# PSDT_Controller_v1_0_0.net
KiCad netlist of a schematic drawn in Altium Designer
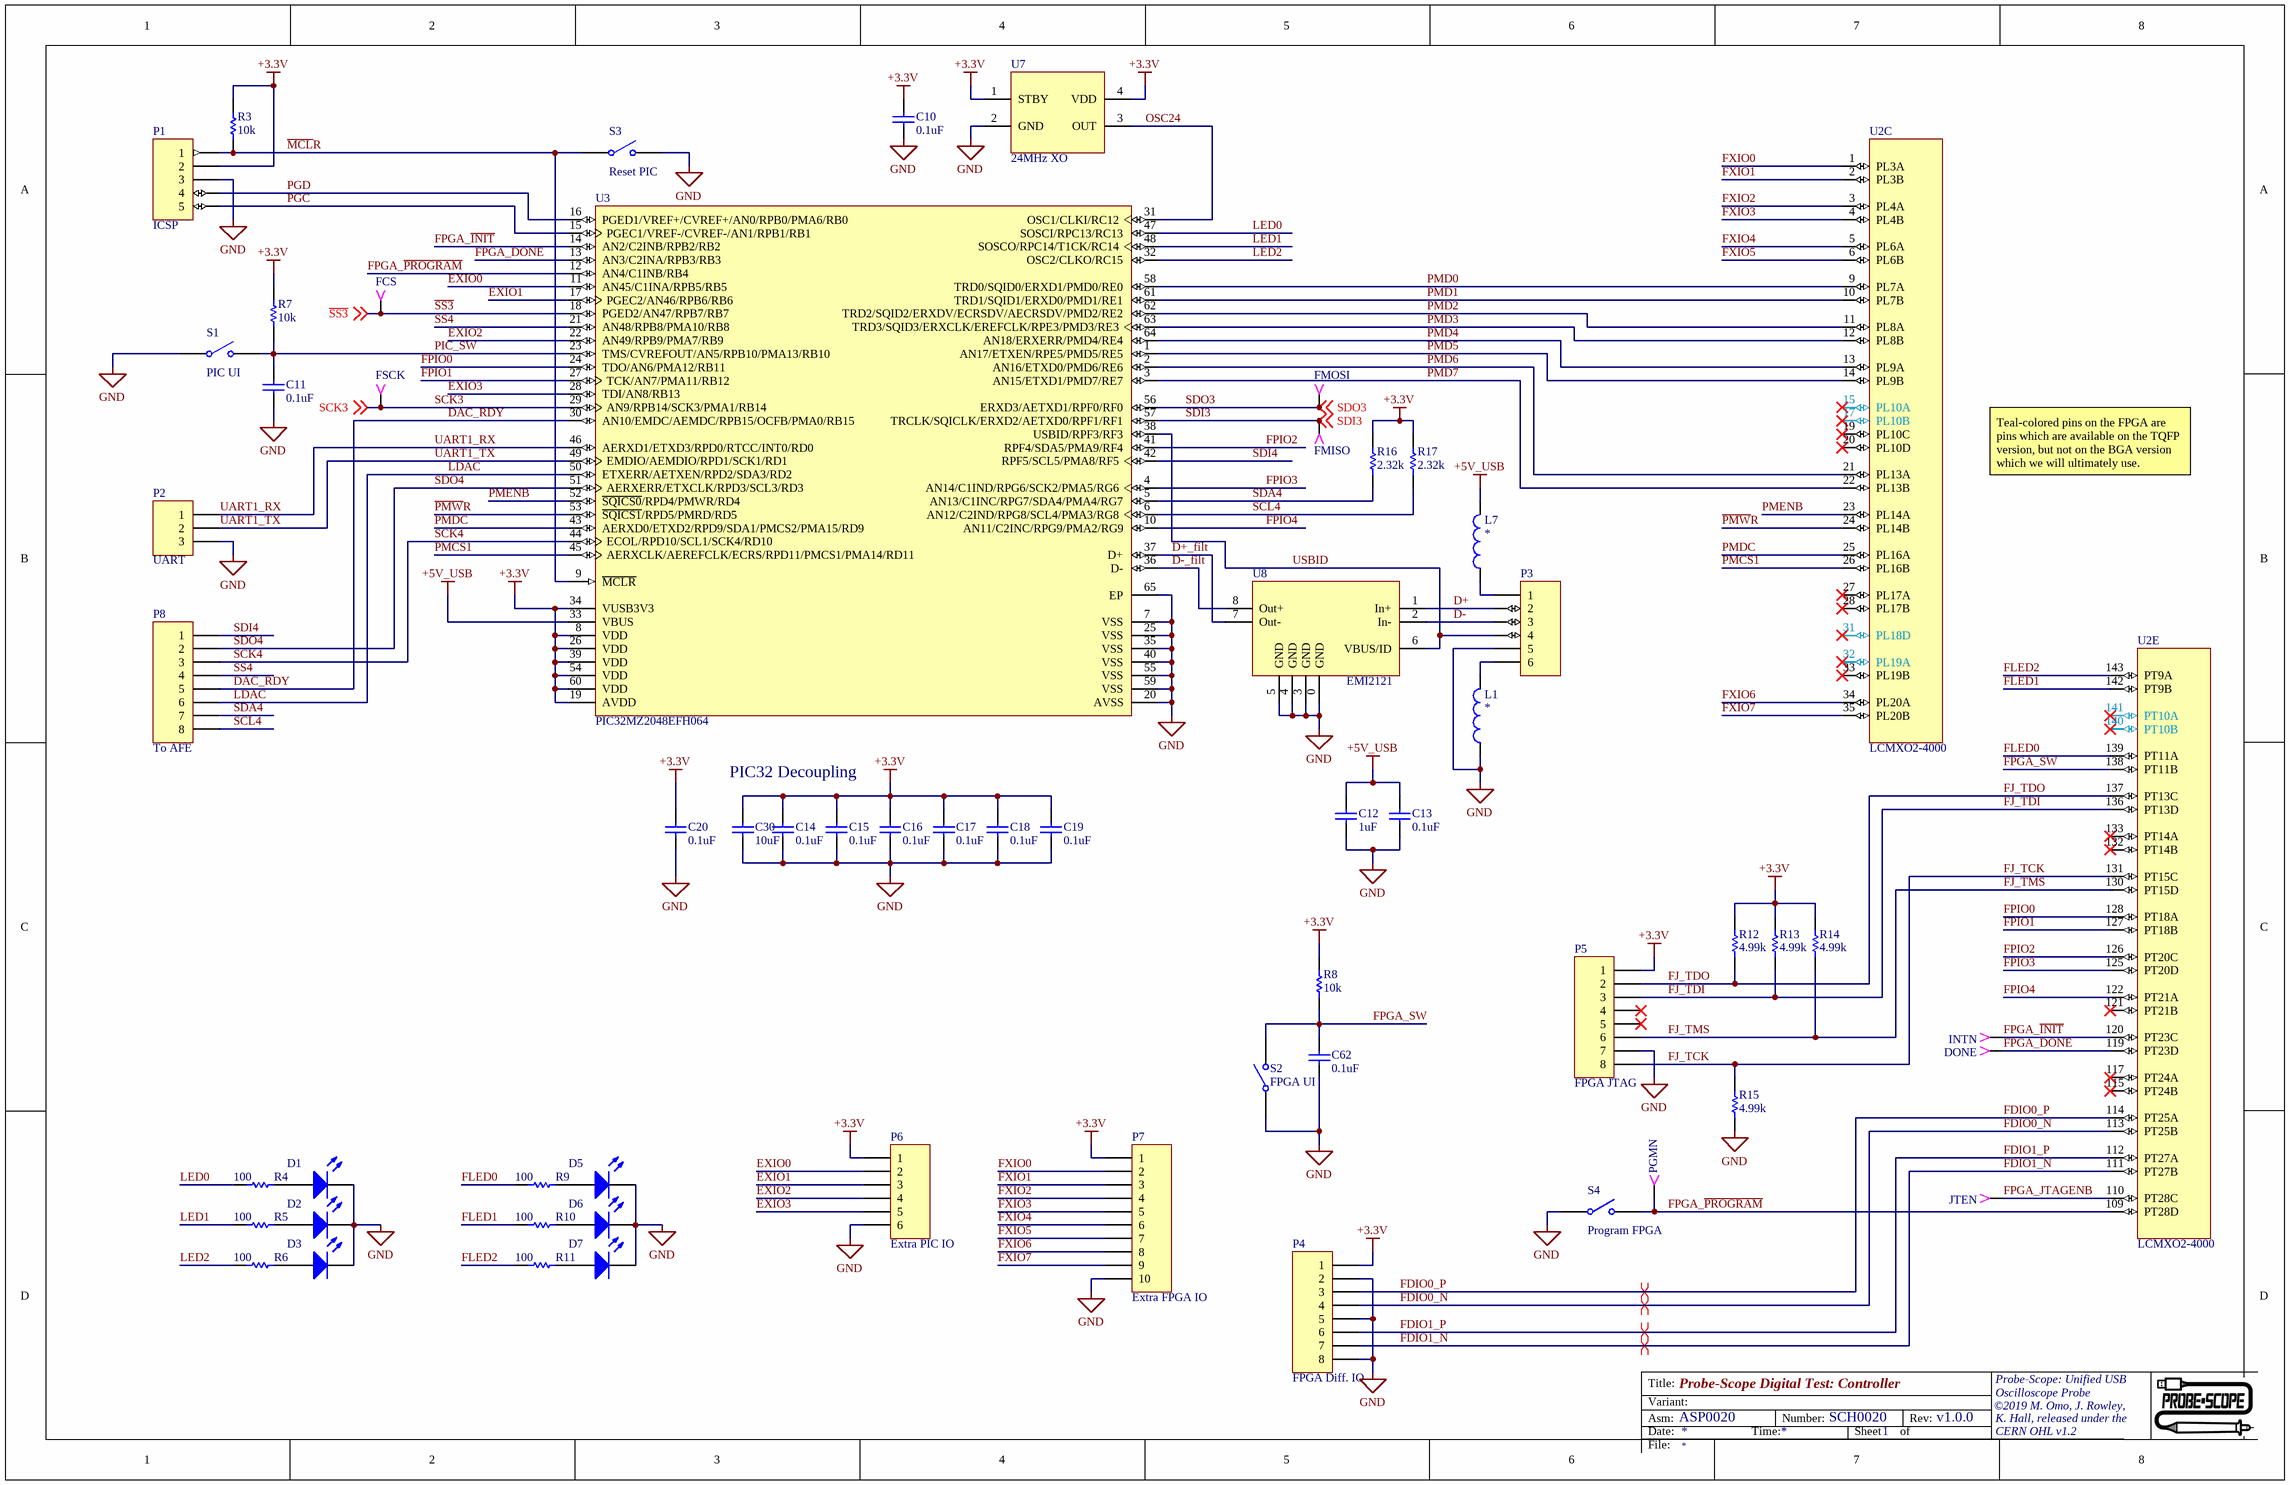
[diagram p0: PSDT Controller v1.0.0.SchDoc]

(export (version "E")
  (design (tool "Eeschema 10.0.6"))
  (components
    (comp (ref "C10")
      (value "0.1uF")
      (footprint "0402(1005)")
      (fields
        (field (name "MANF") "Samsung Electro-Mechanics")
        (field (name "TOLERANCE") "10")
        (field (name "VOLTAGE") "6.3")
        (field (name "MODIFIED BY") "jrowley")
        (field (name "APPROVED") "False")
      )
      (libsource (lib "MENG Database Library VPN") (part "Cap"))
    )
    (comp (ref "C11")
      (value "0.1uF")
      (footprint "0402(1005)")
      (fields
        (field (name "MANF") "Samsung Electro-Mechanics")
        (field (name "TOLERANCE") "10")
        (field (name "VOLTAGE") "6.3")
        (field (name "MODIFIED BY") "jrowley")
        (field (name "APPROVED") "False")
      )
      (libsource (lib "MENG Database Library VPN") (part "Cap"))
    )
    (comp (ref "C12")
      (value "1uF")
      (footprint "0402(1005)")
      (fields
        (field (name "MANF") "Murata Electronics")
        (field (name "TOLERANCE") "10")
        (field (name "Comment") "10V")
        (field (name "MODIFIED BY") "jrowley")
        (field (name "APPROVED") "False")
      )
      (libsource (lib "MENG Database Library VPN") (part "Cap"))
    )
    (comp (ref "C13")
      (value "0.1uF")
      (footprint "0402(1005)")
      (fields
        (field (name "MANF") "Samsung Electro-Mechanics")
        (field (name "TOLERANCE") "10")
        (field (name "VOLTAGE") "6.3")
        (field (name "MODIFIED BY") "jrowley")
        (field (name "APPROVED") "False")
      )
      (libsource (lib "MENG Database Library VPN") (part "Cap"))
    )
    (comp (ref "C14")
      (value "0.1uF")
      (footprint "0402(1005)")
      (fields
        (field (name "MANF") "Samsung Electro-Mechanics")
        (field (name "TOLERANCE") "10")
        (field (name "VOLTAGE") "6.3")
        (field (name "MODIFIED BY") "jrowley")
        (field (name "APPROVED") "False")
      )
      (libsource (lib "MENG Database Library VPN") (part "Cap"))
    )
    (comp (ref "C15")
      (value "0.1uF")
      (footprint "0402(1005)")
      (fields
        (field (name "MANF") "Samsung Electro-Mechanics")
        (field (name "TOLERANCE") "10")
        (field (name "VOLTAGE") "6.3")
        (field (name "MODIFIED BY") "jrowley")
        (field (name "APPROVED") "False")
      )
      (libsource (lib "MENG Database Library VPN") (part "Cap"))
    )
    (comp (ref "C16")
      (value "0.1uF")
      (footprint "0402(1005)")
      (fields
        (field (name "MANF") "Samsung Electro-Mechanics")
        (field (name "TOLERANCE") "10")
        (field (name "VOLTAGE") "6.3")
        (field (name "MODIFIED BY") "jrowley")
        (field (name "APPROVED") "False")
      )
      (libsource (lib "MENG Database Library VPN") (part "Cap"))
    )
    (comp (ref "C17")
      (value "0.1uF")
      (footprint "0402(1005)")
      (fields
        (field (name "MANF") "Samsung Electro-Mechanics")
        (field (name "TOLERANCE") "10")
        (field (name "VOLTAGE") "6.3")
        (field (name "MODIFIED BY") "jrowley")
        (field (name "APPROVED") "False")
      )
      (libsource (lib "MENG Database Library VPN") (part "Cap"))
    )
    (comp (ref "C18")
      (value "0.1uF")
      (footprint "0402(1005)")
      (fields
        (field (name "MANF") "Samsung Electro-Mechanics")
        (field (name "TOLERANCE") "10")
        (field (name "VOLTAGE") "6.3")
        (field (name "MODIFIED BY") "jrowley")
        (field (name "APPROVED") "False")
      )
      (libsource (lib "MENG Database Library VPN") (part "Cap"))
    )
    (comp (ref "C19")
      (value "0.1uF")
      (footprint "0402(1005)")
      (fields
        (field (name "MANF") "Samsung Electro-Mechanics")
        (field (name "TOLERANCE") "10")
        (field (name "VOLTAGE") "6.3")
        (field (name "MODIFIED BY") "jrowley")
        (field (name "APPROVED") "False")
      )
      (libsource (lib "MENG Database Library VPN") (part "Cap"))
    )
    (comp (ref "C20")
      (value "0.1uF")
      (footprint "0402(1005)")
      (fields
        (field (name "MANF") "Samsung Electro-Mechanics")
        (field (name "TOLERANCE") "10")
        (field (name "VOLTAGE") "6.3")
        (field (name "MODIFIED BY") "jrowley")
        (field (name "APPROVED") "False")
      )
      (libsource (lib "MENG Database Library VPN") (part "Cap"))
    )
    (comp (ref "C30")
      (value "10uF")
      (footprint "0603(1608)")
      (fields
        (field (name "MANF") "Samsung Electro-Mechanics")
        (field (name "TOLERANCE") "20")
        (field (name "VOLTAGE") "25")
        (field (name "MODIFIED BY") "sotterbacher")
        (field (name "APPROVED") "True")
      )
      (libsource (lib "MENG Database Library VPN") (part "Cap"))
    )
    (comp (ref "C62")
      (value "0.1uF")
      (footprint "0402(1005)")
      (fields
        (field (name "MANF") "Samsung Electro-Mechanics")
        (field (name "TOLERANCE") "10")
        (field (name "VOLTAGE") "6.3")
        (field (name "MODIFIED BY") "jrowley")
        (field (name "APPROVED") "False")
      )
      (libsource (lib "MENG Database Library VPN") (part "Cap"))
    )
    (comp (ref "D1")
      (value "Green")
      (footprint "0603(1608) LED")
      (fields
        (field (name "MANF") "OSRAM")
        (field (name "VOLTAGE") "1.7")
        (field (name "MODIFIED BY") "pmarcus")
        (field (name "APPROVED") "True")
      )
      (libsource (lib "MENG Database Library VPN") (part "LED0"))
    )
    (comp (ref "D2")
      (value "Green")
      (footprint "0603(1608) LED")
      (fields
        (field (name "MANF") "OSRAM")
        (field (name "VOLTAGE") "1.7")
        (field (name "MODIFIED BY") "pmarcus")
        (field (name "APPROVED") "True")
      )
      (libsource (lib "MENG Database Library VPN") (part "LED0"))
    )
    (comp (ref "D3")
      (value "Green")
      (footprint "0603(1608) LED")
      (fields
        (field (name "MANF") "OSRAM")
        (field (name "VOLTAGE") "1.7")
        (field (name "MODIFIED BY") "pmarcus")
        (field (name "APPROVED") "True")
      )
      (libsource (lib "MENG Database Library VPN") (part "LED0"))
    )
    (comp (ref "D5")
      (value "Green")
      (footprint "0603(1608) LED")
      (fields
        (field (name "MANF") "OSRAM")
        (field (name "VOLTAGE") "1.7")
        (field (name "MODIFIED BY") "pmarcus")
        (field (name "APPROVED") "True")
      )
      (libsource (lib "MENG Database Library VPN") (part "LED0"))
    )
    (comp (ref "D6")
      (value "Green")
      (footprint "0603(1608) LED")
      (fields
        (field (name "MANF") "OSRAM")
        (field (name "VOLTAGE") "1.7")
        (field (name "MODIFIED BY") "pmarcus")
        (field (name "APPROVED") "True")
      )
      (libsource (lib "MENG Database Library VPN") (part "LED0"))
    )
    (comp (ref "D7")
      (value "Green")
      (footprint "0603(1608) LED")
      (fields
        (field (name "MANF") "OSRAM")
        (field (name "VOLTAGE") "1.7")
        (field (name "MODIFIED BY") "pmarcus")
        (field (name "APPROVED") "True")
      )
      (libsource (lib "MENG Database Library VPN") (part "LED0"))
    )
    (comp (ref "DONE")
      (value "TP")
      (footprint "TESTPOINT024")
      (fields
        (field (name "MANF") "Keystone Electronics")
        (field (name "APPROVED") "True")
        (field (name "MODIFIED BY") "sotterbacher")
      )
      (libsource (lib "MENG Database Library VPN") (part "TP"))
    )
    (comp (ref "FCS")
      (value "TP")
      (footprint "TESTPOINT024")
      (fields
        (field (name "MANF") "Keystone Electronics")
        (field (name "APPROVED") "True")
        (field (name "MODIFIED BY") "sotterbacher")
      )
      (libsource (lib "MENG Database Library VPN") (part "TP"))
    )
    (comp (ref "FMISO")
      (value "TP")
      (footprint "TESTPOINT024")
      (fields
        (field (name "MANF") "Keystone Electronics")
        (field (name "APPROVED") "True")
        (field (name "MODIFIED BY") "sotterbacher")
      )
      (libsource (lib "MENG Database Library VPN") (part "TP"))
    )
    (comp (ref "FMOSI")
      (value "TP")
      (footprint "TESTPOINT024")
      (fields
        (field (name "MANF") "Keystone Electronics")
        (field (name "APPROVED") "True")
        (field (name "MODIFIED BY") "sotterbacher")
      )
      (libsource (lib "MENG Database Library VPN") (part "TP"))
    )
    (comp (ref "FSCK")
      (value "TP")
      (footprint "TESTPOINT024")
      (fields
        (field (name "MANF") "Keystone Electronics")
        (field (name "APPROVED") "True")
        (field (name "MODIFIED BY") "sotterbacher")
      )
      (libsource (lib "MENG Database Library VPN") (part "TP"))
    )
    (comp (ref "INTN")
      (value "TP")
      (footprint "TESTPOINT024")
      (fields
        (field (name "MANF") "Keystone Electronics")
        (field (name "APPROVED") "True")
        (field (name "MODIFIED BY") "sotterbacher")
      )
      (libsource (lib "MENG Database Library VPN") (part "TP"))
    )
    (comp (ref "JTEN")
      (value "TP")
      (footprint "TESTPOINT024")
      (fields
        (field (name "MANF") "Keystone Electronics")
        (field (name "APPROVED") "True")
        (field (name "MODIFIED BY") "sotterbacher")
      )
      (libsource (lib "MENG Database Library VPN") (part "TP"))
    )
    (comp (ref "L1")
      (value "Ferrite Bead")
      (footprint "0402(1005)")
      (fields
        (field (name "ALTIUM_VALUE") "*")
        (field (name "MANF") "Murata")
        (field (name "MODIFIED BY") "jrowley")
        (field (name "APPROVED") "False")
      )
      (libsource (lib "MENG Database Library VPN") (part "Inductor"))
    )
    (comp (ref "L7")
      (value "Ferrite Bead")
      (footprint "0402(1005)")
      (fields
        (field (name "ALTIUM_VALUE") "*")
        (field (name "MANF") "Murata")
        (field (name "MODIFIED BY") "jrowley")
        (field (name "APPROVED") "False")
      )
      (libsource (lib "MENG Database Library VPN") (part "Inductor"))
    )
    (comp (ref "P1")
      (value "ICSP")
      (footprint "MOLEX PICOBLADE 5 POS")
      (fields
        (field (name "MANF") "Molex")
        (field (name "VOLTAGE") "125")
        (field (name "MODIFIED BY") "pmarcus")
        (field (name "APPROVED") "True")
      )
      (libsource (lib "MENG Database Library VPN") (part "Header 5"))
    )
    (comp (ref "P2")
      (value "UART")
      (footprint "MOLEX PICOBLADE 3 POS")
      (fields
        (field (name "MANF") "Molex")
        (field (name "VOLTAGE") "125")
        (field (name "MODIFIED BY") "rlaity")
        (field (name "APPROVED") "True")
      )
      (libsource (lib "MENG Database Library VPN") (part "Header 3"))
    )
    (comp (ref "P3")
      (value "Micro USB")
      (footprint "USB Micro B ZX62")
      (fields
        (field (name "MANF") "Amphenol FCI")
        (field (name "VOLTAGE") "100")
        (field (name "MODIFIED BY") "jrowley")
        (field (name "APPROVED") "False")
      )
      (libsource (lib "") (part "Header 6_1"))
    )
    (comp (ref "P4")
      (value "FPGA Diff. IO")
      (footprint "0.1HDR1X8P")
      (fields
        (field (name "MANF") "Molex")
        (field (name "VOLTAGE") "250")
        (field (name "MODIFIED BY") "jrowley")
        (field (name "APPROVED") "False")
      )
      (libsource (lib "MENG Database Library VPN") (part "Header 8"))
    )
    (comp (ref "P5")
      (value "FPGA JTAG")
      (footprint "0.1HDR1X8P")
      (fields
        (field (name "MANF") "Molex")
        (field (name "VOLTAGE") "250")
        (field (name "MODIFIED BY") "jrowley")
        (field (name "APPROVED") "False")
      )
      (libsource (lib "MENG Database Library VPN") (part "Header 8"))
    )
    (comp (ref "P6")
      (value "Extra PIC IO")
      (footprint "0.1HDR1X6P")
      (fields
        (field (name "MANF") "Molex")
        (field (name "VOLTAGE") "250")
        (field (name "MODIFIED BY") "jrowley")
        (field (name "APPROVED") "False")
      )
      (libsource (lib "MENG Database Library VPN") (part "Header 6"))
    )
    (comp (ref "P7")
      (value "Extra FPGA IO")
      (footprint "0.1HDR1X10P")
      (fields
        (field (name "MANF") "Molex")
        (field (name "VOLTAGE") "250")
        (field (name "MODIFIED BY") "jrowley")
        (field (name "APPROVED") "False")
      )
      (libsource (lib "MENG Database Library VPN") (part "Header 10"))
    )
    (comp (ref "P8")
      (value "To AFE")
      (footprint "0.1HDR1X8P")
      (fields
        (field (name "MANF") "Molex")
        (field (name "VOLTAGE") "250")
        (field (name "MODIFIED BY") "jrowley")
        (field (name "APPROVED") "False")
      )
      (libsource (lib "MENG Database Library VPN") (part "Header 8"))
    )
    (comp (ref "PGMN")
      (value "TP")
      (footprint "TESTPOINT024")
      (fields
        (field (name "MANF") "Keystone Electronics")
        (field (name "APPROVED") "True")
        (field (name "MODIFIED BY") "sotterbacher")
      )
      (libsource (lib "MENG Database Library VPN") (part "TP"))
    )
    (comp (ref "R3")
      (value "10k")
      (footprint "0402(1005)")
      (fields
        (field (name "MANF") "Stackpole Electronics")
        (field (name "TOLERANCE") "1")
        (field (name "POWER") "0.0625")
        (field (name "MODIFIED BY") "jrowley")
        (field (name "APPROVED") "False")
      )
      (libsource (lib "MENG Database Library VPN") (part "Res1"))
    )
    (comp (ref "R4")
      (value "100")
      (footprint "0402(1005)")
      (fields
        (field (name "MANF") "Yageo")
        (field (name "TOLERANCE") "1")
        (field (name "POWER") "0.0625")
        (field (name "MODIFIED BY") "jrowley")
        (field (name "APPROVED") "False")
      )
      (libsource (lib "MENG Database Library VPN") (part "Res1"))
    )
    (comp (ref "R5")
      (value "100")
      (footprint "0402(1005)")
      (fields
        (field (name "MANF") "Yageo")
        (field (name "TOLERANCE") "1")
        (field (name "POWER") "0.0625")
        (field (name "MODIFIED BY") "jrowley")
        (field (name "APPROVED") "False")
      )
      (libsource (lib "MENG Database Library VPN") (part "Res1"))
    )
    (comp (ref "R6")
      (value "100")
      (footprint "0402(1005)")
      (fields
        (field (name "MANF") "Yageo")
        (field (name "TOLERANCE") "1")
        (field (name "POWER") "0.0625")
        (field (name "MODIFIED BY") "jrowley")
        (field (name "APPROVED") "False")
      )
      (libsource (lib "MENG Database Library VPN") (part "Res1"))
    )
    (comp (ref "R7")
      (value "10k")
      (footprint "0402(1005)")
      (fields
        (field (name "MANF") "Stackpole Electronics")
        (field (name "TOLERANCE") "1")
        (field (name "POWER") "0.0625")
        (field (name "MODIFIED BY") "jrowley")
        (field (name "APPROVED") "False")
      )
      (libsource (lib "MENG Database Library VPN") (part "Res1"))
    )
    (comp (ref "R8")
      (value "10k")
      (footprint "0402(1005)")
      (fields
        (field (name "MANF") "Stackpole Electronics")
        (field (name "TOLERANCE") "1")
        (field (name "POWER") "0.0625")
        (field (name "MODIFIED BY") "jrowley")
        (field (name "APPROVED") "False")
      )
      (libsource (lib "MENG Database Library VPN") (part "Res1"))
    )
    (comp (ref "R9")
      (value "100")
      (footprint "0402(1005)")
      (fields
        (field (name "MANF") "Yageo")
        (field (name "TOLERANCE") "1")
        (field (name "POWER") "0.0625")
        (field (name "MODIFIED BY") "jrowley")
        (field (name "APPROVED") "False")
      )
      (libsource (lib "MENG Database Library VPN") (part "Res1"))
    )
    (comp (ref "R10")
      (value "100")
      (footprint "0402(1005)")
      (fields
        (field (name "MANF") "Yageo")
        (field (name "TOLERANCE") "1")
        (field (name "POWER") "0.0625")
        (field (name "MODIFIED BY") "jrowley")
        (field (name "APPROVED") "False")
      )
      (libsource (lib "MENG Database Library VPN") (part "Res1"))
    )
    (comp (ref "R11")
      (value "100")
      (footprint "0402(1005)")
      (fields
        (field (name "MANF") "Yageo")
        (field (name "TOLERANCE") "1")
        (field (name "POWER") "0.0625")
        (field (name "MODIFIED BY") "jrowley")
        (field (name "APPROVED") "False")
      )
      (libsource (lib "MENG Database Library VPN") (part "Res1"))
    )
    (comp (ref "R12")
      (value "4.99k")
      (footprint "0402(1005)")
      (fields
        (field (name "MANF") "Yageo")
        (field (name "TOLERANCE") "1")
        (field (name "POWER") "0.063")
        (field (name "MODIFIED BY") "khall")
        (field (name "APPROVED") "False")
      )
      (libsource (lib "MENG Database Library VPN") (part "Res1"))
    )
    (comp (ref "R13")
      (value "4.99k")
      (footprint "0402(1005)")
      (fields
        (field (name "MANF") "Yageo")
        (field (name "TOLERANCE") "1")
        (field (name "POWER") "0.063")
        (field (name "MODIFIED BY") "khall")
        (field (name "APPROVED") "False")
      )
      (libsource (lib "MENG Database Library VPN") (part "Res1"))
    )
    (comp (ref "R14")
      (value "4.99k")
      (footprint "0402(1005)")
      (fields
        (field (name "MANF") "Yageo")
        (field (name "TOLERANCE") "1")
        (field (name "POWER") "0.063")
        (field (name "MODIFIED BY") "khall")
        (field (name "APPROVED") "False")
      )
      (libsource (lib "MENG Database Library VPN") (part "Res1"))
    )
    (comp (ref "R15")
      (value "4.99k")
      (footprint "0402(1005)")
      (fields
        (field (name "MANF") "Yageo")
        (field (name "TOLERANCE") "1")
        (field (name "POWER") "0.063")
        (field (name "MODIFIED BY") "khall")
        (field (name "APPROVED") "False")
      )
      (libsource (lib "MENG Database Library VPN") (part "Res1"))
    )
    (comp (ref "R16")
      (value "2.32k")
      (footprint "0402(1005)")
      (fields
        (field (name "MANF") "Stackpole Electronics")
        (field (name "TOLERANCE") "1")
        (field (name "POWER") "0.0625")
        (field (name "MODIFIED BY") "khall")
        (field (name "APPROVED") "False")
      )
      (libsource (lib "MENG Database Library VPN") (part "Res1"))
    )
    (comp (ref "R17")
      (value "2.32k")
      (footprint "0402(1005)")
      (fields
        (field (name "MANF") "Stackpole Electronics")
        (field (name "TOLERANCE") "1")
        (field (name "POWER") "0.0625")
        (field (name "MODIFIED BY") "khall")
        (field (name "APPROVED") "False")
      )
      (libsource (lib "MENG Database Library VPN") (part "Res1"))
    )
    (comp (ref "S1")
      (value "PIC UI")
      (footprint "PTS645 SMT")
      (fields
        (field (name "MANF") "C&K Components")
        (field (name "MODIFIED BY") "jrowley")
        (field (name "APPROVED") "False")
      )
      (libsource (lib "MENG Database Library VPN") (part "SW-SPST"))
    )
    (comp (ref "S2")
      (value "FPGA UI")
      (footprint "PTS645 SMT")
      (fields
        (field (name "MANF") "C&K Components")
        (field (name "MODIFIED BY") "jrowley")
        (field (name "APPROVED") "False")
      )
      (libsource (lib "MENG Database Library VPN") (part "SW-SPST"))
    )
    (comp (ref "S3")
      (value "Reset PIC")
      (footprint "PTS645 SMT")
      (fields
        (field (name "MANF") "C&K Components")
        (field (name "MODIFIED BY") "jrowley")
        (field (name "APPROVED") "False")
      )
      (libsource (lib "MENG Database Library VPN") (part "SW-SPST"))
    )
    (comp (ref "S4")
      (value "Program FPGA")
      (footprint "PTS645 SMT")
      (fields
        (field (name "MANF") "C&K Components")
        (field (name "MODIFIED BY") "jrowley")
        (field (name "APPROVED") "False")
      )
      (libsource (lib "MENG Database Library VPN") (part "SW-SPST"))
    )
    (comp (ref "U2")
      (value "LCMXO2-4000")
      (footprint "UL_TQFP144")
      (fields (field (name "MANF") "Lattice Semiconductor Corporation"))
      (libsource (lib "PS") (part "MachXO2-4000-TG144"))
    )
    (comp (ref "U3")
      (value "PIC32MZ2048EFH064")
      (footprint "QFN50P900X900-64N")
      (description "Microchip PIC32MZ EF Series 64-pin")
      (fields (field (name "MANF") "Microchip Technology"))
      (libsource (lib "PS") (part "PIC32MZ2048EFH064-I/PT"))
    )
    (comp (ref "U7")
      (value "24MHz XO")
      (footprint "DSC60xxC")
      (fields
        (field (name "MANF") "Microchip")
        (field (name "MODIFIED BY") "jrowley")
        (field (name "APPROVED") "False")
      )
      (libsource (lib "MENG Database Library VPN") (part "DSC60x1"))
    )
    (comp (ref "U8")
      (value "EMI2121")
      (footprint "EMI2121")
      (fields
        (field (name "MANF") "On Semiconductor")
        (field (name "MODIFIED BY") "jrowley")
        (field (name "APPROVED") "False")
      )
      (libsource (lib "MENG Database Library VPN") (part "EMI2121"))
    )
  )
  (nets
    (net (code "1") (name "+3.3V") (class "Default")
      (node (ref "C10") (pin "2") (pinfunction "2_2") (pintype "passive"))
      (node (ref "C14") (pin "2") (pinfunction "2_2") (pintype "passive"))
      (node (ref "C15") (pin "2") (pinfunction "2_2") (pintype "passive"))
      (node (ref "C16") (pin "2") (pinfunction "2_2") (pintype "passive"))
      (node (ref "C17") (pin "2") (pinfunction "2_2") (pintype "passive"))
      (node (ref "C18") (pin "2") (pinfunction "2_2") (pintype "passive"))
      (node (ref "C19") (pin "2") (pinfunction "2_2") (pintype "passive"))
      (node (ref "C20") (pin "2") (pinfunction "2_2") (pintype "passive"))
      (node (ref "C30") (pin "2") (pinfunction "2_2") (pintype "passive"))
      (node (ref "P1") (pin "2") (pinfunction "2_2") (pintype "power_in"))
      (node (ref "P4") (pin "1") (pinfunction "1_1") (pintype "passive"))
      (node (ref "P5") (pin "1") (pinfunction "1_1") (pintype "passive"))
      (node (ref "P6") (pin "1") (pinfunction "1_1") (pintype "passive"))
      (node (ref "P7") (pin "1") (pinfunction "1_1") (pintype "passive"))
      (node (ref "R12") (pin "2") (pinfunction "2_2") (pintype "passive"))
      (node (ref "R13") (pin "2") (pinfunction "2_2") (pintype "passive"))
      (node (ref "R14") (pin "2") (pinfunction "2_2") (pintype "passive"))
      (node (ref "R16") (pin "2") (pinfunction "2_2") (pintype "passive"))
      (node (ref "R17") (pin "2") (pinfunction "2_2") (pintype "passive"))
      (node (ref "R3") (pin "2") (pinfunction "2_2") (pintype "passive"))
      (node (ref "R7") (pin "1") (pinfunction "1_1") (pintype "passive"))
      (node (ref "R8") (pin "1") (pinfunction "1_1") (pintype "passive"))
      (node (ref "U3") (pin "19") (pinfunction "AVDD_19") (pintype "power_in"))
      (node (ref "U3") (pin "26") (pinfunction "VDD_26") (pintype "power_in"))
      (node (ref "U3") (pin "34") (pinfunction "VUSB3V3_34") (pintype "power_in"))
      (node (ref "U3") (pin "39") (pinfunction "VDD_39") (pintype "power_in"))
      (node (ref "U3") (pin "54") (pinfunction "VDD_54") (pintype "power_in"))
      (node (ref "U3") (pin "60") (pinfunction "VDD_60") (pintype "power_in"))
      (node (ref "U3") (pin "8") (pinfunction "VDD_8") (pintype "power_in"))
      (node (ref "U7") (pin "1") (pinfunction "STBY_1") (pintype "passive"))
      (node (ref "U7") (pin "4") (pinfunction "VDD_4") (pintype "passive"))
    )
    (net (code "2") (name "+5V_USB") (class "Default")
      (node (ref "C12") (pin "2") (pinfunction "2_2") (pintype "passive"))
      (node (ref "C13") (pin "2") (pinfunction "2_2") (pintype "passive"))
      (node (ref "L7") (pin "2") (pinfunction "2_2") (pintype "passive"))
      (node (ref "U3") (pin "33") (pinfunction "VBUS_33") (pintype "power_in"))
    )
    (net (code "3") (name "/D+") (class "Default")
      (node (ref "P3") (pin "2") (pinfunction "2_2") (pintype "bidirectional"))
      (node (ref "U8") (pin "1") (pinfunction "In+_1") (pintype "passive"))
    )
    (net (code "4") (name "/D+_filt") (class "Default")
      (node (ref "U3") (pin "37") (pinfunction "D+_37") (pintype "bidirectional"))
      (node (ref "U8") (pin "7") (pinfunction "Out-_7") (pintype "passive"))
    )
    (net (code "5") (name "/D-") (class "Default")
      (node (ref "P3") (pin "3") (pinfunction "3_3") (pintype "bidirectional"))
      (node (ref "U8") (pin "2") (pinfunction "In-_2") (pintype "passive"))
    )
    (net (code "6") (name "/D-_filt") (class "Default")
      (node (ref "U3") (pin "36") (pinfunction "D-_36") (pintype "bidirectional"))
      (node (ref "U8") (pin "8") (pinfunction "Out+_8") (pintype "passive"))
    )
    (net (code "7") (name "/DAC_RDY") (class "Default")
      (node (ref "P8") (pin "5") (pinfunction "5_5") (pintype "passive"))
      (node (ref "U3") (pin "30") (pinfunction "AN10/EMDC/AEMDC/RPB15/OCFB/PMA0/RB15_30") (pintype "bidirectional"))
    )
    (net (code "8") (name "/EXIO0") (class "Default")
      (node (ref "P6") (pin "2") (pinfunction "2_2") (pintype "passive"))
      (node (ref "U3") (pin "11") (pinfunction "AN45/C1INA/RPB5/RB5_11") (pintype "bidirectional"))
    )
    (net (code "9") (name "/EXIO1") (class "Default")
      (node (ref "P6") (pin "3") (pinfunction "3_3") (pintype "passive"))
      (node (ref "U3") (pin "17") (pinfunction "PGEC2/AN46/RPB6/RB6_17") (pintype "bidirectional"))
    )
    (net (code "10") (name "/EXIO2") (class "Default")
      (node (ref "P6") (pin "4") (pinfunction "4_4") (pintype "passive"))
      (node (ref "U3") (pin "22") (pinfunction "AN49/RPB9/PMA7/RB9_22") (pintype "bidirectional"))
    )
    (net (code "11") (name "/EXIO3") (class "Default")
      (node (ref "P6") (pin "5") (pinfunction "5_5") (pintype "passive"))
      (node (ref "U3") (pin "28") (pinfunction "TDI/AN8/RB13_28") (pintype "bidirectional"))
    )
    (net (code "12") (name "/FDIO0_N") (class "Default")
      (node (ref "P4") (pin "4") (pinfunction "4_4") (pintype "passive"))
      (node (ref "U2") (pin "113") (pinfunction "PT25B_113") (pintype "bidirectional"))
    )
    (net (code "13") (name "/FDIO0_P") (class "Default")
      (node (ref "P4") (pin "3") (pinfunction "3_3") (pintype "passive"))
      (node (ref "U2") (pin "114") (pinfunction "PT25A_114") (pintype "bidirectional"))
    )
    (net (code "14") (name "/FDIO1_N") (class "Default")
      (node (ref "P4") (pin "7") (pinfunction "7_7") (pintype "passive"))
      (node (ref "U2") (pin "111") (pinfunction "PT27B_111") (pintype "bidirectional"))
    )
    (net (code "15") (name "/FDIO1_P") (class "Default")
      (node (ref "P4") (pin "6") (pinfunction "6_6") (pintype "passive"))
      (node (ref "U2") (pin "112") (pinfunction "PT27A_112") (pintype "bidirectional"))
    )
    (net (code "16") (name "/FJ_TCK") (class "Default")
      (node (ref "P5") (pin "8") (pinfunction "8_8") (pintype "passive"))
      (node (ref "R15") (pin "2") (pinfunction "2_2") (pintype "passive"))
      (node (ref "U2") (pin "131") (pinfunction "PT15C_131") (pintype "bidirectional"))
    )
    (net (code "17") (name "/FJ_TDI") (class "Default")
      (node (ref "P5") (pin "3") (pinfunction "3_3") (pintype "passive"))
      (node (ref "R13") (pin "1") (pinfunction "1_1") (pintype "passive"))
      (node (ref "U2") (pin "136") (pinfunction "PT13D_136") (pintype "bidirectional"))
    )
    (net (code "18") (name "/FJ_TDO") (class "Default")
      (node (ref "P5") (pin "2") (pinfunction "2_2") (pintype "passive"))
      (node (ref "R12") (pin "1") (pinfunction "1_1") (pintype "passive"))
      (node (ref "U2") (pin "137") (pinfunction "PT13C_137") (pintype "bidirectional"))
    )
    (net (code "19") (name "/FJ_TMS") (class "Default")
      (node (ref "P5") (pin "6") (pinfunction "6_6") (pintype "passive"))
      (node (ref "R14") (pin "1") (pinfunction "1_1") (pintype "passive"))
      (node (ref "U2") (pin "130") (pinfunction "PT15D_130") (pintype "bidirectional"))
    )
    (net (code "20") (name "/FLED0") (class "Default")
      (node (ref "R9") (pin "1") (pinfunction "1_1") (pintype "passive"))
      (node (ref "U2") (pin "139") (pinfunction "PT11A_139") (pintype "bidirectional"))
    )
    (net (code "21") (name "/FLED1") (class "Default")
      (node (ref "R10") (pin "1") (pinfunction "1_1") (pintype "passive"))
      (node (ref "U2") (pin "142") (pinfunction "PT9B_142") (pintype "bidirectional"))
    )
    (net (code "22") (name "/FLED2") (class "Default")
      (node (ref "R11") (pin "1") (pinfunction "1_1") (pintype "passive"))
      (node (ref "U2") (pin "143") (pinfunction "PT9A_143") (pintype "bidirectional"))
    )
    (net (code "23") (name "/FPGA_DONE") (class "Default")
      (node (ref "DONE") (pin "1") (pinfunction "1_1") (pintype "passive"))
      (node (ref "U2") (pin "119") (pinfunction "PT23D_119") (pintype "bidirectional"))
      (node (ref "U3") (pin "13") (pinfunction "AN3/C2INA/RPB3/RB3_13") (pintype "bidirectional"))
    )
    (net (code "24") (name "/FPGA_JTAGENB") (class "Default")
      (node (ref "JTEN") (pin "1") (pinfunction "1_1") (pintype "passive"))
      (node (ref "U2") (pin "110") (pinfunction "PT28C_110") (pintype "bidirectional"))
    )
    (net (code "25") (name "/FPGA_SW") (class "Default")
      (node (ref "C62") (pin "2") (pinfunction "2_2") (pintype "passive"))
      (node (ref "R8") (pin "2") (pinfunction "2_2") (pintype "passive"))
      (node (ref "S2") (pin "2") (pinfunction "NO_2") (pintype "passive"))
      (node (ref "U2") (pin "138") (pinfunction "PT11B_138") (pintype "bidirectional"))
    )
    (net (code "26") (name "/FPGA_~{INIT}") (class "Default")
      (node (ref "INTN") (pin "1") (pinfunction "1_1") (pintype "passive"))
      (node (ref "U2") (pin "120") (pinfunction "PT23C_120") (pintype "bidirectional"))
      (node (ref "U3") (pin "14") (pinfunction "AN2/C2INB/RPB2/RB2_14") (pintype "bidirectional"))
    )
    (net (code "27") (name "/FPGA_~{PROGRAM}") (class "Default")
      (node (ref "PGMN") (pin "1") (pinfunction "1_1") (pintype "passive"))
      (node (ref "S4") (pin "2") (pinfunction "NO_2") (pintype "passive"))
      (node (ref "U2") (pin "109") (pinfunction "PT28D_109") (pintype "bidirectional"))
      (node (ref "U3") (pin "12") (pinfunction "AN4/C1INB/RB4_12") (pintype "bidirectional"))
    )
    (net (code "28") (name "/FPIO0") (class "Default")
      (node (ref "U2") (pin "128") (pinfunction "PT18A_128") (pintype "bidirectional"))
      (node (ref "U3") (pin "24") (pinfunction "TDO/AN6/PMA12/RB11_24") (pintype "bidirectional"))
    )
    (net (code "29") (name "/FPIO1") (class "Default")
      (node (ref "U2") (pin "127") (pinfunction "PT18B_127") (pintype "bidirectional"))
      (node (ref "U3") (pin "27") (pinfunction "TCK/AN7/PMA11/RB12_27") (pintype "bidirectional"))
    )
    (net (code "30") (name "/FPIO2") (class "Default")
      (node (ref "U2") (pin "126") (pinfunction "PT20C_126") (pintype "bidirectional"))
      (node (ref "U3") (pin "41") (pinfunction "RPF4/SDA5/PMA9/RF4_41") (pintype "bidirectional"))
    )
    (net (code "31") (name "/FPIO3") (class "Default")
      (node (ref "U2") (pin "125") (pinfunction "PT20D_125") (pintype "bidirectional"))
      (node (ref "U3") (pin "4") (pinfunction "AN14/C1IND/RPG6/SCK2/PMA5/RG6_4") (pintype "bidirectional"))
    )
    (net (code "32") (name "/FPIO4") (class "Default")
      (node (ref "U2") (pin "122") (pinfunction "PT21A_122") (pintype "bidirectional"))
      (node (ref "U3") (pin "10") (pinfunction "AN11/C2INC/RPG9/PMA2/RG9_10") (pintype "bidirectional"))
    )
    (net (code "33") (name "/FXIO0") (class "Default")
      (node (ref "P7") (pin "2") (pinfunction "2_2") (pintype "passive"))
      (node (ref "U2") (pin "1") (pinfunction "PL3A_1") (pintype "bidirectional"))
    )
    (net (code "34") (name "/FXIO1") (class "Default")
      (node (ref "P7") (pin "3") (pinfunction "3_3") (pintype "passive"))
      (node (ref "U2") (pin "2") (pinfunction "PL3B_2") (pintype "bidirectional"))
    )
    (net (code "35") (name "/FXIO2") (class "Default")
      (node (ref "P7") (pin "4") (pinfunction "4_4") (pintype "passive"))
      (node (ref "U2") (pin "3") (pinfunction "PL4A_3") (pintype "bidirectional"))
    )
    (net (code "36") (name "/FXIO3") (class "Default")
      (node (ref "P7") (pin "5") (pinfunction "5_5") (pintype "passive"))
      (node (ref "U2") (pin "4") (pinfunction "PL4B_4") (pintype "bidirectional"))
    )
    (net (code "37") (name "/FXIO4") (class "Default")
      (node (ref "P7") (pin "6") (pinfunction "6_6") (pintype "passive"))
      (node (ref "U2") (pin "5") (pinfunction "PL6A_5") (pintype "bidirectional"))
    )
    (net (code "38") (name "/FXIO5") (class "Default")
      (node (ref "P7") (pin "7") (pinfunction "7_7") (pintype "passive"))
      (node (ref "U2") (pin "6") (pinfunction "PL6B_6") (pintype "bidirectional"))
    )
    (net (code "39") (name "/FXIO6") (class "Default")
      (node (ref "P7") (pin "8") (pinfunction "8_8") (pintype "passive"))
      (node (ref "U2") (pin "34") (pinfunction "PL20A_34") (pintype "bidirectional"))
    )
    (net (code "40") (name "/FXIO7") (class "Default")
      (node (ref "P7") (pin "9") (pinfunction "9_9") (pintype "passive"))
      (node (ref "U2") (pin "35") (pinfunction "PL20B_35") (pintype "bidirectional"))
    )
    (net (code "41") (name "/LED0") (class "Default")
      (node (ref "R4") (pin "1") (pinfunction "1_1") (pintype "passive"))
      (node (ref "U3") (pin "47") (pinfunction "SOSCI/RPC13/RC13_47") (pintype "bidirectional"))
    )
    (net (code "42") (name "/LED1") (class "Default")
      (node (ref "R5") (pin "1") (pinfunction "1_1") (pintype "passive"))
      (node (ref "U3") (pin "48") (pinfunction "SOSCO/RPC14/T1CK/RC14_48") (pintype "bidirectional"))
    )
    (net (code "43") (name "/LED2") (class "Default")
      (node (ref "R6") (pin "1") (pinfunction "1_1") (pintype "passive"))
      (node (ref "U3") (pin "32") (pinfunction "OSC2/CLKO/RC15_32") (pintype "bidirectional"))
    )
    (net (code "44") (name "/OSC24") (class "Default")
      (node (ref "U3") (pin "31") (pinfunction "OSC1/CLKI/RC12_31") (pintype "bidirectional"))
      (node (ref "U7") (pin "3") (pinfunction "OUT_3") (pintype "passive"))
    )
    (net (code "45") (name "/PGC") (class "Default")
      (node (ref "P1") (pin "5") (pinfunction "5_5") (pintype "bidirectional"))
      (node (ref "U3") (pin "15") (pinfunction "PGEC1/VREF-/CVREF-/AN1/RPB1/RB1_15") (pintype "bidirectional"))
    )
    (net (code "46") (name "/PGD") (class "Default")
      (node (ref "P1") (pin "4") (pinfunction "4_4") (pintype "bidirectional"))
      (node (ref "U3") (pin "16") (pinfunction "PGED1/VREF+/CVREF+/AN0/RPB0/PMA6/RB0_16") (pintype "bidirectional"))
    )
    (net (code "47") (name "/PIC_SW") (class "Default")
      (node (ref "C11") (pin "2") (pinfunction "2_2") (pintype "passive"))
      (node (ref "R7") (pin "2") (pinfunction "2_2") (pintype "passive"))
      (node (ref "S1") (pin "2") (pinfunction "NO_2") (pintype "passive"))
      (node (ref "U3") (pin "23") (pinfunction "TMS/CVREFOUT/AN5/RPB10/PMA13/RB10_23") (pintype "bidirectional"))
    )
    (net (code "48") (name "/PMCS1") (class "Default")
      (node (ref "U2") (pin "26") (pinfunction "PL16B_26") (pintype "bidirectional"))
      (node (ref "U3") (pin "45") (pinfunction "AERXCLK/AEREFCLK/ECRS/RPD11/PMCS1/PMA14/RD11_45") (pintype "bidirectional"))
    )
    (net (code "49") (name "/PMD0") (class "Default")
      (node (ref "U2") (pin "9") (pinfunction "PL7A_9") (pintype "bidirectional"))
      (node (ref "U3") (pin "58") (pinfunction "TRD0/SQID0/ERXD1/PMD0/RE0_58") (pintype "bidirectional"))
    )
    (net (code "50") (name "/PMD1") (class "Default")
      (node (ref "U2") (pin "10") (pinfunction "PL7B_10") (pintype "bidirectional"))
      (node (ref "U3") (pin "61") (pinfunction "TRD1/SQID1/ERXD0/PMD1/RE1_61") (pintype "bidirectional"))
    )
    (net (code "51") (name "/PMD2") (class "Default")
      (node (ref "U2") (pin "11") (pinfunction "PL8A_11") (pintype "bidirectional"))
      (node (ref "U3") (pin "62") (pinfunction "TRD2/SQID2/ERXDV/ECRSDV/AECRSDV/PMD2/RE2_62") (pintype "bidirectional"))
    )
    (net (code "52") (name "/PMD3") (class "Default")
      (node (ref "U2") (pin "12") (pinfunction "PL8B_12") (pintype "bidirectional"))
      (node (ref "U3") (pin "63") (pinfunction "TRD3/SQID3/ERXCLK/EREFCLK/RPE3/PMD3/RE3_63") (pintype "bidirectional"))
    )
    (net (code "53") (name "/PMD4") (class "Default")
      (node (ref "U2") (pin "13") (pinfunction "PL9A_13") (pintype "bidirectional"))
      (node (ref "U3") (pin "64") (pinfunction "AN18/ERXERR/PMD4/RE4_64") (pintype "bidirectional"))
    )
    (net (code "54") (name "/PMD5") (class "Default")
      (node (ref "U2") (pin "14") (pinfunction "PL9B_14") (pintype "bidirectional"))
      (node (ref "U3") (pin "1") (pinfunction "AN17/ETXEN/RPE5/PMD5/RE5_1") (pintype "bidirectional"))
    )
    (net (code "55") (name "/PMD6") (class "Default")
      (node (ref "U2") (pin "21") (pinfunction "PL13A_21") (pintype "bidirectional"))
      (node (ref "U3") (pin "2") (pinfunction "AN16/ETXD0/PMD6/RE6_2") (pintype "bidirectional"))
    )
    (net (code "56") (name "/PMD7") (class "Default")
      (node (ref "U2") (pin "22") (pinfunction "PL13B_22") (pintype "bidirectional"))
      (node (ref "U3") (pin "3") (pinfunction "AN15/ETXD1/PMD7/RE7_3") (pintype "bidirectional"))
    )
    (net (code "57") (name "/PMDC") (class "Default")
      (node (ref "U2") (pin "25") (pinfunction "PL16A_25") (pintype "bidirectional"))
      (node (ref "U3") (pin "43") (pinfunction "AERXD0/ETXD2/RPD9/SDA1/PMCS2/PMA15/RD9_43") (pintype "bidirectional"))
    )
    (net (code "58") (name "/PMENB") (class "Default")
      (node (ref "U2") (pin "23") (pinfunction "PL14A_23") (pintype "bidirectional"))
      (node (ref "U3") (pin "52") (pinfunction "~{SQICS0}/RPD4/PMWR/RD4_52") (pintype "bidirectional"))
    )
    (net (code "59") (name "/SCK4") (class "Default")
      (node (ref "P8") (pin "3") (pinfunction "3_3") (pintype "passive"))
      (node (ref "U3") (pin "44") (pinfunction "ECOL/RPD10/SCL1/SCK4/RD10_44") (pintype "bidirectional"))
    )
    (net (code "60") (name "/SCL4") (class "Default")
      (node (ref "P8") (pin "8") (pinfunction "8_8") (pintype "passive"))
      (node (ref "R17") (pin "1") (pinfunction "1_1") (pintype "passive"))
      (node (ref "U3") (pin "6") (pinfunction "AN12/C2IND/RPG8/SCL4/PMA3/RG8_6") (pintype "bidirectional"))
    )
    (net (code "61") (name "/SDA4") (class "Default")
      (node (ref "P8") (pin "7") (pinfunction "7_7") (pintype "passive"))
      (node (ref "R16") (pin "1") (pinfunction "1_1") (pintype "passive"))
      (node (ref "U3") (pin "5") (pinfunction "AN13/C1INC/RPG7/SDA4/PMA4/RG7_5") (pintype "bidirectional"))
    )
    (net (code "62") (name "/SDI4") (class "Default")
      (node (ref "P8") (pin "1") (pinfunction "1_1") (pintype "passive"))
      (node (ref "U3") (pin "42") (pinfunction "RPF5/SCL5/PMA8/RF5_42") (pintype "bidirectional"))
    )
    (net (code "63") (name "/SDO4") (class "Default")
      (node (ref "P8") (pin "2") (pinfunction "2_2") (pintype "passive"))
      (node (ref "U3") (pin "51") (pinfunction "AERXERR/ETXCLK/RPD3/SCL3/RD3_51") (pintype "bidirectional"))
    )
    (net (code "64") (name "/UART1_RX") (class "Default")
      (node (ref "P2") (pin "1") (pinfunction "1_1") (pintype "passive"))
      (node (ref "U3") (pin "46") (pinfunction "AERXD1/ETXD3/RPD0/RTCC/INT0/RD0_46") (pintype "bidirectional"))
    )
    (net (code "65") (name "/UART1_TX") (class "Default")
      (node (ref "P2") (pin "2") (pinfunction "2_2") (pintype "passive"))
      (node (ref "U3") (pin "49") (pinfunction "EMDIO/AEMDIO/RPD1/SCK1/RD1_49") (pintype "bidirectional"))
    )
    (net (code "66") (name "/USBID") (class "Default")
      (node (ref "P3") (pin "4") (pinfunction "4_4") (pintype "bidirectional"))
      (node (ref "U3") (pin "38") (pinfunction "USBID/RPF3/RF3_38") (pintype "bidirectional"))
      (node (ref "U8") (pin "6") (pinfunction "VBUS/ID_6") (pintype "passive"))
    )
    (net (code "67") (name "/~{LDAC}") (class "Default")
      (node (ref "P8") (pin "6") (pinfunction "6_6") (pintype "passive"))
      (node (ref "U3") (pin "50") (pinfunction "ETXERR/AETXEN/RPD2/SDA3/RD2_50") (pintype "bidirectional"))
    )
    (net (code "68") (name "/~{MCL}R") (class "Default")
      (node (ref "P1") (pin "1") (pinfunction "1_1") (pintype "output"))
      (node (ref "R3") (pin "1") (pinfunction "1_1") (pintype "passive"))
      (node (ref "S3") (pin "1") (pinfunction "COMMON_1") (pintype "passive"))
      (node (ref "U3") (pin "9") (pinfunction "~{MCLR}_9") (pintype "input"))
    )
    (net (code "69") (name "/~{PMW}R") (class "Default")
      (node (ref "U2") (pin "24") (pinfunction "PL14B_24") (pintype "bidirectional"))
      (node (ref "U3") (pin "53") (pinfunction "~{SQICS1}/RPD5/PMRD/RD5_53") (pintype "bidirectional"))
    )
    (net (code "70") (name "/~{SS4}") (class "Default")
      (node (ref "P8") (pin "4") (pinfunction "4_4") (pintype "passive"))
      (node (ref "U3") (pin "21") (pinfunction "AN48/RPB8/PMA10/RB8_21") (pintype "bidirectional"))
    )
    (net (code "71") (name "GND") (class "Default")
      (node (ref "C10") (pin "1") (pinfunction "1_1") (pintype "passive"))
      (node (ref "C11") (pin "1") (pinfunction "1_1") (pintype "passive"))
      (node (ref "C12") (pin "1") (pinfunction "1_1") (pintype "passive"))
      (node (ref "C13") (pin "1") (pinfunction "1_1") (pintype "passive"))
      (node (ref "C14") (pin "1") (pinfunction "1_1") (pintype "passive"))
      (node (ref "C15") (pin "1") (pinfunction "1_1") (pintype "passive"))
      (node (ref "C16") (pin "1") (pinfunction "1_1") (pintype "passive"))
      (node (ref "C17") (pin "1") (pinfunction "1_1") (pintype "passive"))
      (node (ref "C18") (pin "1") (pinfunction "1_1") (pintype "passive"))
      (node (ref "C19") (pin "1") (pinfunction "1_1") (pintype "passive"))
      (node (ref "C20") (pin "1") (pinfunction "1_1") (pintype "passive"))
      (node (ref "C30") (pin "1") (pinfunction "1_1") (pintype "passive"))
      (node (ref "C62") (pin "1") (pinfunction "1_1") (pintype "passive"))
      (node (ref "D1") (pin "2") (pinfunction "K_2") (pintype "passive"))
      (node (ref "D2") (pin "2") (pinfunction "K_2") (pintype "passive"))
      (node (ref "D3") (pin "2") (pinfunction "K_2") (pintype "passive"))
      (node (ref "D5") (pin "2") (pinfunction "K_2") (pintype "passive"))
      (node (ref "D6") (pin "2") (pinfunction "K_2") (pintype "passive"))
      (node (ref "D7") (pin "2") (pinfunction "K_2") (pintype "passive"))
      (node (ref "L1") (pin "1") (pinfunction "1_1") (pintype "passive"))
      (node (ref "P1") (pin "3") (pinfunction "3_3") (pintype "power_in"))
      (node (ref "P2") (pin "3") (pinfunction "3_3") (pintype "passive"))
      (node (ref "P3") (pin "5") (pinfunction "5_5") (pintype "power_in"))
      (node (ref "P4") (pin "2") (pinfunction "2_2") (pintype "passive"))
      (node (ref "P4") (pin "5") (pinfunction "5_5") (pintype "passive"))
      (node (ref "P4") (pin "8") (pinfunction "8_8") (pintype "passive"))
      (node (ref "P5") (pin "7") (pinfunction "7_7") (pintype "passive"))
      (node (ref "P6") (pin "6") (pinfunction "6_6") (pintype "passive"))
      (node (ref "P7") (pin "10") (pinfunction "10_10") (pintype "passive"))
      (node (ref "R15") (pin "1") (pinfunction "1_1") (pintype "passive"))
      (node (ref "S1") (pin "1") (pinfunction "COMMON_1") (pintype "passive"))
      (node (ref "S2") (pin "1") (pinfunction "COMMON_1") (pintype "passive"))
      (node (ref "S3") (pin "2") (pinfunction "NO_2") (pintype "passive"))
      (node (ref "S4") (pin "1") (pinfunction "COMMON_1") (pintype "passive"))
      (node (ref "U3") (pin "20") (pinfunction "AVSS_20") (pintype "power_in"))
      (node (ref "U3") (pin "25") (pinfunction "VSS_25") (pintype "power_in"))
      (node (ref "U3") (pin "35") (pinfunction "VSS_35") (pintype "power_in"))
      (node (ref "U3") (pin "40") (pinfunction "VSS_40") (pintype "power_in"))
      (node (ref "U3") (pin "55") (pinfunction "VSS_55") (pintype "power_in"))
      (node (ref "U3") (pin "59") (pinfunction "VSS_59") (pintype "power_in"))
      (node (ref "U3") (pin "65") (pinfunction "EP_65") (pintype "power_in"))
      (node (ref "U3") (pin "7") (pinfunction "VSS_7") (pintype "power_in"))
      (node (ref "U7") (pin "2") (pinfunction "GND_2") (pintype "passive"))
      (node (ref "U8") (pin "0") (pinfunction "GND_0") (pintype "passive"))
      (node (ref "U8") (pin "3") (pinfunction "GND_3") (pintype "passive"))
      (node (ref "U8") (pin "4") (pinfunction "GND_4") (pintype "passive"))
      (node (ref "U8") (pin "5") (pinfunction "GND_5") (pintype "passive"))
    )
    (net (code "72") (name "Net-(D1-A)") (class "Default")
      (node (ref "D1") (pin "1") (pinfunction "A_1") (pintype "passive"))
      (node (ref "R4") (pin "2") (pinfunction "2_2") (pintype "passive"))
    )
    (net (code "73") (name "Net-(D2-A)") (class "Default")
      (node (ref "D2") (pin "1") (pinfunction "A_1") (pintype "passive"))
      (node (ref "R5") (pin "2") (pinfunction "2_2") (pintype "passive"))
    )
    (net (code "74") (name "Net-(D3-A)") (class "Default")
      (node (ref "D3") (pin "1") (pinfunction "A_1") (pintype "passive"))
      (node (ref "R6") (pin "2") (pinfunction "2_2") (pintype "passive"))
    )
    (net (code "75") (name "Net-(D5-A)") (class "Default")
      (node (ref "D5") (pin "1") (pinfunction "A_1") (pintype "passive"))
      (node (ref "R9") (pin "2") (pinfunction "2_2") (pintype "passive"))
    )
    (net (code "76") (name "Net-(D6-A)") (class "Default")
      (node (ref "D6") (pin "1") (pinfunction "A_1") (pintype "passive"))
      (node (ref "R10") (pin "2") (pinfunction "2_2") (pintype "passive"))
    )
    (net (code "77") (name "Net-(D7-A)") (class "Default")
      (node (ref "D7") (pin "1") (pinfunction "A_1") (pintype "passive"))
      (node (ref "R11") (pin "2") (pinfunction "2_2") (pintype "passive"))
    )
    (net (code "78") (name "Net-(L1-Pad2)") (class "Default")
      (node (ref "L1") (pin "2") (pinfunction "2_2") (pintype "passive"))
      (node (ref "P3") (pin "6") (pinfunction "6_6") (pintype "passive"))
    )
    (net (code "79") (name "Net-(L7-Pad1)") (class "Default")
      (node (ref "L7") (pin "1") (pinfunction "1_1") (pintype "passive"))
      (node (ref "P3") (pin "1") (pinfunction "1_1") (pintype "power_in"))
    )
    (net (code "80") (name "SCK3") (class "Default")
      (node (ref "FSCK") (pin "1") (pinfunction "1_1") (pintype "passive"))
      (node (ref "U3") (pin "29") (pinfunction "AN9/RPB14/SCK3/PMA1/RB14_29") (pintype "bidirectional"))
    )
    (net (code "81") (name "SDI3") (class "Default")
      (node (ref "FMISO") (pin "1") (pinfunction "1_1") (pintype "passive"))
      (node (ref "U3") (pin "57") (pinfunction "TRCLK/SQICLK/ERXD2/AETXD0/RPF1/RF1_57") (pintype "bidirectional"))
    )
    (net (code "82") (name "SDO3") (class "Default")
      (node (ref "FMOSI") (pin "1") (pinfunction "1_1") (pintype "passive"))
      (node (ref "U3") (pin "56") (pinfunction "ERXD3/AETXD1/RPF0/RF0_56") (pintype "bidirectional"))
    )
    (net (code "83") (name "unconnected-(P5-Pad4)") (class "Default")
      (node (ref "P5") (pin "4") (pinfunction "4_4") (pintype "passive+no_connect"))
    )
    (net (code "84") (name "unconnected-(P5-Pad5)") (class "Default")
      (node (ref "P5") (pin "5") (pinfunction "5_5") (pintype "passive+no_connect"))
    )
    (net (code "85") (name "unconnected-(U2C-PL10A-Pad15)") (class "Default")
      (node (ref "U2") (pin "15") (pinfunction "PL10A_15") (pintype "bidirectional+no_connect"))
    )
    (net (code "86") (name "unconnected-(U2C-PL10B-Pad17)") (class "Default")
      (node (ref "U2") (pin "17") (pinfunction "PL10B_17") (pintype "bidirectional+no_connect"))
    )
    (net (code "87") (name "unconnected-(U2C-PL10C-Pad19)") (class "Default")
      (node (ref "U2") (pin "19") (pinfunction "PL10C_19") (pintype "bidirectional+no_connect"))
    )
    (net (code "88") (name "unconnected-(U2C-PL10D-Pad20)") (class "Default")
      (node (ref "U2") (pin "20") (pinfunction "PL10D_20") (pintype "bidirectional+no_connect"))
    )
    (net (code "89") (name "unconnected-(U2C-PL17A-Pad27)") (class "Default")
      (node (ref "U2") (pin "27") (pinfunction "PL17A_27") (pintype "bidirectional+no_connect"))
    )
    (net (code "90") (name "unconnected-(U2C-PL17B-Pad28)") (class "Default")
      (node (ref "U2") (pin "28") (pinfunction "PL17B_28") (pintype "bidirectional+no_connect"))
    )
    (net (code "91") (name "unconnected-(U2C-PL18D-Pad31)") (class "Default")
      (node (ref "U2") (pin "31") (pinfunction "PL18D_31") (pintype "bidirectional+no_connect"))
    )
    (net (code "92") (name "unconnected-(U2C-PL19A-Pad32)") (class "Default")
      (node (ref "U2") (pin "32") (pinfunction "PL19A_32") (pintype "bidirectional+no_connect"))
    )
    (net (code "93") (name "unconnected-(U2C-PL19B-Pad33)") (class "Default")
      (node (ref "U2") (pin "33") (pinfunction "PL19B_33") (pintype "bidirectional+no_connect"))
    )
    (net (code "94") (name "unconnected-(U2E-PT10A-Pad141)") (class "Default")
      (node (ref "U2") (pin "141") (pinfunction "PT10A_141") (pintype "bidirectional+no_connect"))
    )
    (net (code "95") (name "unconnected-(U2E-PT10B-Pad140)") (class "Default")
      (node (ref "U2") (pin "140") (pinfunction "PT10B_140") (pintype "bidirectional+no_connect"))
    )
    (net (code "96") (name "unconnected-(U2E-PT14A-Pad133)") (class "Default")
      (node (ref "U2") (pin "133") (pinfunction "PT14A_133") (pintype "bidirectional+no_connect"))
    )
    (net (code "97") (name "unconnected-(U2E-PT14B-Pad132)") (class "Default")
      (node (ref "U2") (pin "132") (pinfunction "PT14B_132") (pintype "bidirectional+no_connect"))
    )
    (net (code "98") (name "unconnected-(U2E-PT21B-Pad121)") (class "Default")
      (node (ref "U2") (pin "121") (pinfunction "PT21B_121") (pintype "bidirectional+no_connect"))
    )
    (net (code "99") (name "unconnected-(U2E-PT24A-Pad117)") (class "Default")
      (node (ref "U2") (pin "117") (pinfunction "PT24A_117") (pintype "bidirectional+no_connect"))
    )
    (net (code "100") (name "unconnected-(U2E-PT24B-Pad115)") (class "Default")
      (node (ref "U2") (pin "115") (pinfunction "PT24B_115") (pintype "bidirectional+no_connect"))
    )
    (net (code "101") (name "~{SS3}") (class "Default")
      (node (ref "FCS") (pin "1") (pinfunction "1_1") (pintype "passive"))
      (node (ref "U3") (pin "18") (pinfunction "PGED2/AN47/RPB7/RB7_18") (pintype "bidirectional"))
    )
  )
)
